# GCS.net
KiCad netlist of a schematic drawn in EAGLE
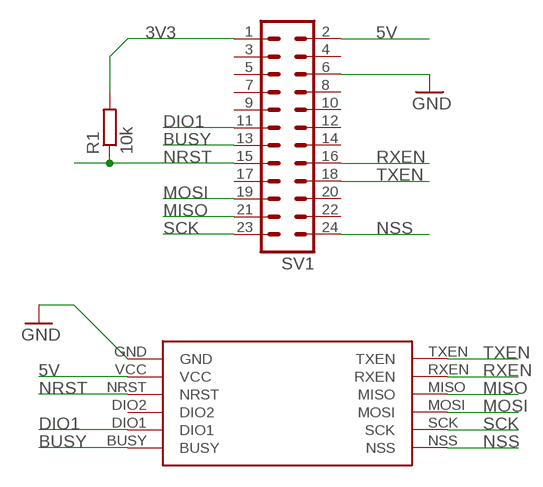
[diagram p0: schematic, sheet 1]

(export (version "E")
  (design (tool "Eeschema 10.0.6"))
  (components
    (comp (ref "R1")
      (value "10k")
      (footprint "eagle-import:0207_10")
      (libsource (lib "eagle-import") (part "R-EU_0207/10"))
    )
    (comp (ref "SV1")
      (value "MA12-2")
      (footprint "eagle-import:MA12-2")
      (libsource (lib "eagle-import") (part "MA12-2"))
    )
    (comp (ref "U$1")
      (value "E22_PLATE")
      (footprint "eagle-import:E22_PLATE")
      (libsource (lib "eagle-import") (part "E22_PLATE"))
    )
  )
  (nets
    (net (code "1") (name "/3V3") (class "Default")
      (node (ref "R1") (pin "2") (pinfunction "2_2") (pintype "passive"))
      (node (ref "SV1") (pin "1") (pinfunction "1_1") (pintype "passive"))
    )
    (net (code "2") (name "/5V") (class "Default")
      (node (ref "SV1") (pin "2") (pinfunction "2_2") (pintype "passive"))
      (node (ref "U$1") (pin "VCC") (pinfunction "VCC_VCC") (pintype "bidirectional"))
    )
    (net (code "3") (name "/BUSY") (class "Default")
      (node (ref "SV1") (pin "13") (pinfunction "13_13") (pintype "passive"))
      (node (ref "U$1") (pin "BUSY") (pinfunction "BUSY_BUSY") (pintype "bidirectional"))
    )
    (net (code "4") (name "/DIO1") (class "Default")
      (node (ref "SV1") (pin "11") (pinfunction "11_11") (pintype "passive"))
      (node (ref "U$1") (pin "DIO1") (pinfunction "DIO1_DIO1") (pintype "bidirectional"))
    )
    (net (code "5") (name "/MISO") (class "Default")
      (node (ref "SV1") (pin "21") (pinfunction "21_21") (pintype "passive"))
      (node (ref "U$1") (pin "MISO") (pinfunction "MISO_MISO") (pintype "bidirectional"))
    )
    (net (code "6") (name "/MOSI") (class "Default")
      (node (ref "SV1") (pin "19") (pinfunction "19_19") (pintype "passive"))
      (node (ref "U$1") (pin "MOSI") (pinfunction "MOSI_MOSI") (pintype "bidirectional"))
    )
    (net (code "7") (name "/NRST") (class "Default")
      (node (ref "R1") (pin "1") (pinfunction "1_1") (pintype "passive"))
      (node (ref "SV1") (pin "15") (pinfunction "15_15") (pintype "passive"))
      (node (ref "U$1") (pin "NRST") (pinfunction "NRST_NRST") (pintype "bidirectional"))
    )
    (net (code "8") (name "/NSS") (class "Default")
      (node (ref "SV1") (pin "24") (pinfunction "24_24") (pintype "passive"))
      (node (ref "U$1") (pin "NSS") (pinfunction "NSS_NSS") (pintype "bidirectional"))
    )
    (net (code "9") (name "/RXEN") (class "Default")
      (node (ref "SV1") (pin "16") (pinfunction "16_16") (pintype "passive"))
      (node (ref "U$1") (pin "RXEN") (pinfunction "RXEN_RXEN") (pintype "bidirectional"))
    )
    (net (code "10") (name "/SCK") (class "Default")
      (node (ref "SV1") (pin "23") (pinfunction "23_23") (pintype "passive"))
      (node (ref "U$1") (pin "SCK") (pinfunction "SCK_SCK") (pintype "bidirectional"))
    )
    (net (code "11") (name "/TXEN") (class "Default")
      (node (ref "SV1") (pin "18") (pinfunction "18_18") (pintype "passive"))
      (node (ref "U$1") (pin "TXEN") (pinfunction "TXEN_TXEN") (pintype "bidirectional"))
    )
    (net (code "12") (name "GND") (class "Default")
      (node (ref "SV1") (pin "6") (pinfunction "6_6") (pintype "passive"))
      (node (ref "U$1") (pin "GND") (pinfunction "GND_GND") (pintype "bidirectional"))
    )
    (net (code "13") (name "unconnected-(SV1-Pad3)") (class "Default")
      (node (ref "SV1") (pin "3") (pinfunction "3_3") (pintype "passive"))
    )
    (net (code "14") (name "unconnected-(SV1-Pad4)") (class "Default")
      (node (ref "SV1") (pin "4") (pinfunction "4_4") (pintype "passive"))
    )
    (net (code "15") (name "unconnected-(SV1-Pad5)") (class "Default")
      (node (ref "SV1") (pin "5") (pinfunction "5_5") (pintype "passive"))
    )
    (net (code "16") (name "unconnected-(SV1-Pad7)") (class "Default")
      (node (ref "SV1") (pin "7") (pinfunction "7_7") (pintype "passive"))
    )
    (net (code "17") (name "unconnected-(SV1-Pad8)") (class "Default")
      (node (ref "SV1") (pin "8") (pinfunction "8_8") (pintype "passive"))
    )
    (net (code "18") (name "unconnected-(SV1-Pad9)") (class "Default")
      (node (ref "SV1") (pin "9") (pinfunction "9_9") (pintype "passive"))
    )
    (net (code "19") (name "unconnected-(SV1-Pad10)") (class "Default")
      (node (ref "SV1") (pin "10") (pinfunction "10_10") (pintype "passive"))
    )
    (net (code "20") (name "unconnected-(SV1-Pad12)") (class "Default")
      (node (ref "SV1") (pin "12") (pinfunction "12_12") (pintype "passive"))
    )
    (net (code "21") (name "unconnected-(SV1-Pad14)") (class "Default")
      (node (ref "SV1") (pin "14") (pinfunction "14_14") (pintype "passive"))
    )
    (net (code "22") (name "unconnected-(SV1-Pad17)") (class "Default")
      (node (ref "SV1") (pin "17") (pinfunction "17_17") (pintype "passive"))
    )
    (net (code "23") (name "unconnected-(SV1-Pad20)") (class "Default")
      (node (ref "SV1") (pin "20") (pinfunction "20_20") (pintype "passive"))
    )
    (net (code "24") (name "unconnected-(SV1-Pad22)") (class "Default")
      (node (ref "SV1") (pin "22") (pinfunction "22_22") (pintype "passive"))
    )
    (net (code "25") (name "unconnected-(U$1-PadDIO2)") (class "Default")
      (node (ref "U$1") (pin "DIO2") (pinfunction "DIO2_DIO2") (pintype "bidirectional"))
    )
  )
)
